# HamOrcaBoard.net
KiCad netlist of a schematic drawn in EAGLE
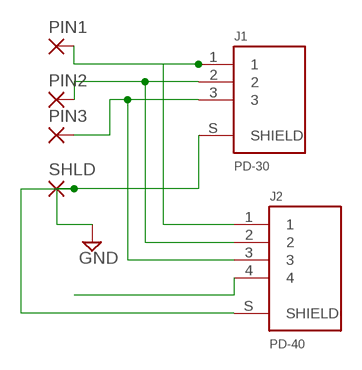
[diagram p0: schematic, sheet 1]

(export (version "E")
  (design (tool "Eeschema 10.0.6"))
  (components
    (comp (ref "J1")
      (value "PD-30")
      (footprint "eagle-import:CUI_PD-30")
      (fields (field (name "MF") "CUI Inc"))
      (libsource (lib "eagle-import") (part "PD-30"))
    )
    (comp (ref "J2")
      (value "PD-40")
      (footprint "eagle-import:CUI_PD-40")
      (fields (field (name "MF") "CUI Inc"))
      (libsource (lib "eagle-import") (part "PD-40"))
    )
    (comp (ref "PIN1")
      (value "3,81/1,4")
      (footprint "eagle-import:3,81_1,4")
      (libsource (lib "eagle-import") (part "3,81/1,4"))
    )
    (comp (ref "PIN2")
      (value "3,81/1,4")
      (footprint "eagle-import:3,81_1,4")
      (libsource (lib "eagle-import") (part "3,81/1,4"))
    )
    (comp (ref "PIN3")
      (value "3,81/1,4")
      (footprint "eagle-import:3,81_1,4")
      (libsource (lib "eagle-import") (part "3,81/1,4"))
    )
    (comp (ref "SHLD")
      (value "3,81/1,4")
      (footprint "eagle-import:3,81_1,4")
      (libsource (lib "eagle-import") (part "3,81/1,4"))
    )
  )
  (nets
    (net (code "1") (name "GND") (class "Default")
      (node (ref "J1") (pin "S") (pinfunction "SHIELD_S") (pintype "passive"))
      (node (ref "J2") (pin "S") (pinfunction "SHIELD_S") (pintype "passive"))
      (node (ref "SHLD") (pin "1") (pinfunction "P_1") (pintype "passive"))
    )
    (net (code "2") (name "Net-(PIN1-P)") (class "Default")
      (node (ref "J1") (pin "1") (pinfunction "1_1") (pintype "passive"))
      (node (ref "J2") (pin "1") (pinfunction "1_1") (pintype "passive"))
      (node (ref "PIN1") (pin "1") (pinfunction "P_1") (pintype "passive"))
    )
    (net (code "3") (name "Net-(PIN2-P)") (class "Default")
      (node (ref "J1") (pin "2") (pinfunction "2_2") (pintype "passive"))
      (node (ref "J2") (pin "2") (pinfunction "2_2") (pintype "passive"))
      (node (ref "PIN2") (pin "1") (pinfunction "P_1") (pintype "passive"))
    )
    (net (code "4") (name "Net-(PIN3-P)") (class "Default")
      (node (ref "J1") (pin "3") (pinfunction "3_3") (pintype "passive"))
      (node (ref "J2") (pin "3") (pinfunction "3_3") (pintype "passive"))
      (node (ref "PIN3") (pin "1") (pinfunction "P_1") (pintype "passive"))
    )
    (net (code "5") (name "unconnected-(J2-Pad4)") (class "Default")
      (node (ref "J2") (pin "4") (pinfunction "4_4") (pintype "passive"))
    )
  )
)
